# exp_5.net
KiCad netlist of a schematic drawn in EAGLE
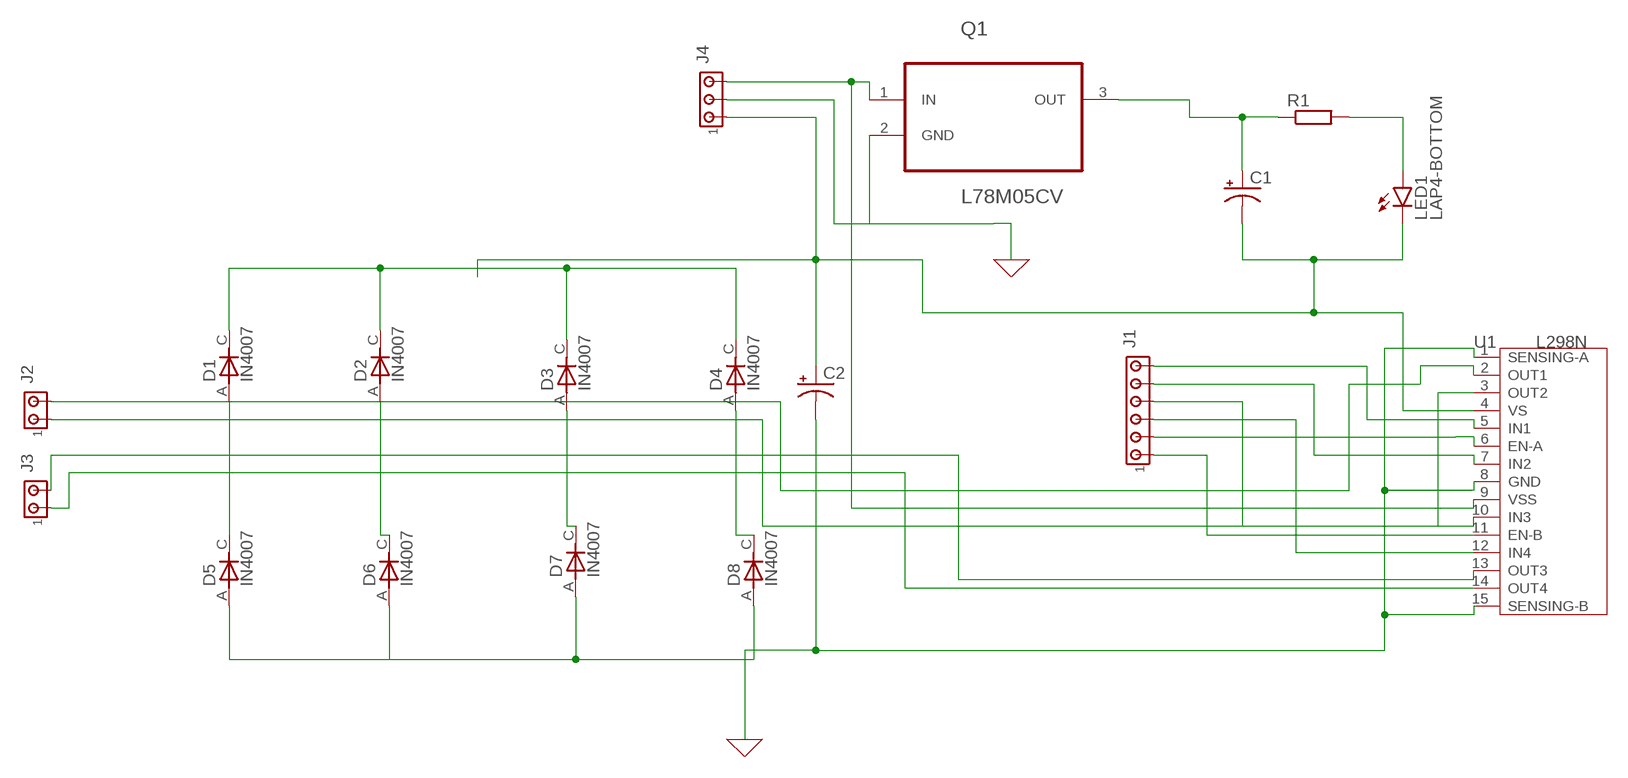
[diagram p0: schematic, sheet 1]

(export (version "E")
  (design (tool "Eeschema 10.0.6"))
  (components
    (comp (ref "C1")
      (value "CPOL-US085CS-1AR")
      (footprint "eagle-import:085CS_1AR")
      (libsource (lib "eagle-import") (part "CPOL-US085CS-1AR"))
    )
    (comp (ref "C2")
      (value "CPOL-US085CS-1AR")
      (footprint "eagle-import:085CS_1AR")
      (libsource (lib "eagle-import") (part "CPOL-US085CS-1AR"))
    )
    (comp (ref "D1")
      (value "IN4007")
      (footprint "eagle-import:DIOAD1070W78L470D235P")
      (fields (field (name "MF") "Vishay Semiconductor"))
      (libsource (lib "eagle-import") (part "IN4007"))
    )
    (comp (ref "D2")
      (value "IN4007")
      (footprint "eagle-import:DIOAD1070W78L470D235P")
      (fields (field (name "MF") "Vishay Semiconductor"))
      (libsource (lib "eagle-import") (part "IN4007"))
    )
    (comp (ref "D3")
      (value "IN4007")
      (footprint "eagle-import:DIOAD1070W78L470D235P")
      (fields (field (name "MF") "Vishay Semiconductor"))
      (libsource (lib "eagle-import") (part "IN4007"))
    )
    (comp (ref "D4")
      (value "IN4007")
      (footprint "eagle-import:DIOAD1070W78L470D235P")
      (fields (field (name "MF") "Vishay Semiconductor"))
      (libsource (lib "eagle-import") (part "IN4007"))
    )
    (comp (ref "D5")
      (value "IN4007")
      (footprint "eagle-import:DIOAD1070W78L470D235P")
      (fields (field (name "MF") "Vishay Semiconductor"))
      (libsource (lib "eagle-import") (part "IN4007"))
    )
    (comp (ref "D6")
      (value "IN4007")
      (footprint "eagle-import:DIOAD1070W78L470D235P")
      (fields (field (name "MF") "Vishay Semiconductor"))
      (libsource (lib "eagle-import") (part "IN4007"))
    )
    (comp (ref "D7")
      (value "IN4007")
      (footprint "eagle-import:DIOAD1070W78L470D235P")
      (fields (field (name "MF") "Vishay Semiconductor"))
      (libsource (lib "eagle-import") (part "IN4007"))
    )
    (comp (ref "D8")
      (value "IN4007")
      (footprint "eagle-import:DIOAD1070W78L470D235P")
      (fields (field (name "MF") "Vishay Semiconductor"))
      (libsource (lib "eagle-import") (part "IN4007"))
    )
    (comp (ref "J1")
      (value "MTA06-100")
      (footprint "eagle-import:10X06MTA")
      (libsource (lib "eagle-import") (part "MTA06-100"))
    )
    (comp (ref "J2")
      (value "MTA02-100")
      (footprint "eagle-import:10X02MTA")
      (libsource (lib "eagle-import") (part "MTA02-100"))
    )
    (comp (ref "J3")
      (value "MTA02-100")
      (footprint "eagle-import:10X02MTA")
      (libsource (lib "eagle-import") (part "MTA02-100"))
    )
    (comp (ref "J4")
      (value "MTA03-100")
      (footprint "eagle-import:10X03MTA")
      (libsource (lib "eagle-import") (part "MTA03-100"))
    )
    (comp (ref "LED1")
      (value "LAP4-BOTTOM")
      (footprint "eagle-import:P47F-BOTTOM")
      (libsource (lib "eagle-import") (part "P4-BOTTOMLA"))
    )
    (comp (ref "Q1")
      (value "L78M05CV")
      (footprint "eagle-import:TO254P450X1020X1935-3P")
      (fields (field (name "MF") "STMicroelectronics") (field (name "MP") "L78M05CV."))
      (libsource (lib "eagle-import") (part "L78M05CV"))
    )
    (comp (ref "R1")
      (value "R-EU_0204/2V")
      (footprint "eagle-import:0204V")
      (libsource (lib "eagle-import") (part "R-EU_0204/2V"))
    )
    (comp (ref "U1")
      (value "L298N")
      (footprint "eagle-import:MULTIWATT15-V")
      (fields (field (name "MF") "4tronix"))
      (libsource (lib "eagle-import") (part "L298N"))
    )
  )
  (nets
    (net (code "1") (name "GND") (class "Default")
      (node (ref "C2") (pin "-") (pinfunction "-_-") (pintype "passive"))
      (node (ref "J4") (pin "2") (pinfunction "2_2") (pintype "passive"))
      (node (ref "Q1") (pin "2") (pinfunction "GND_2") (pintype "passive"))
      (node (ref "U1") (pin "1") (pinfunction "SENSING-A_1") (pintype "bidirectional"))
      (node (ref "U1") (pin "15") (pinfunction "SENSING-B_15") (pintype "bidirectional"))
      (node (ref "U1") (pin "8") (pinfunction "GND_8") (pintype "power_in"))
    )
    (net (code "2") (name "Net-(D1-PadA)") (class "Default")
      (node (ref "D1") (pin "A") (pinfunction "A_A") (pintype "passive"))
      (node (ref "D5") (pin "C") (pinfunction "C_C") (pintype "passive"))
    )
    (net (code "3") (name "Net-(D1-PadC)") (class "Default")
      (node (ref "D1") (pin "C") (pinfunction "C_C") (pintype "passive"))
      (node (ref "D2") (pin "C") (pinfunction "C_C") (pintype "passive"))
      (node (ref "D3") (pin "C") (pinfunction "C_C") (pintype "passive"))
      (node (ref "D4") (pin "C") (pinfunction "C_C") (pintype "passive"))
    )
    (net (code "4") (name "Net-(D2-PadA)") (class "Default")
      (node (ref "D2") (pin "A") (pinfunction "A_A") (pintype "passive"))
      (node (ref "D6") (pin "C") (pinfunction "C_C") (pintype "passive"))
    )
    (net (code "5") (name "Net-(D3-PadA)") (class "Default")
      (node (ref "D3") (pin "A") (pinfunction "A_A") (pintype "passive"))
      (node (ref "D7") (pin "C") (pinfunction "C_C") (pintype "passive"))
    )
    (net (code "6") (name "Net-(D4-PadA)") (class "Default")
      (node (ref "D4") (pin "A") (pinfunction "A_A") (pintype "passive"))
      (node (ref "D8") (pin "C") (pinfunction "C_C") (pintype "passive"))
    )
    (net (code "7") (name "Net-(D5-PadA)") (class "Default")
      (node (ref "D5") (pin "A") (pinfunction "A_A") (pintype "passive"))
      (node (ref "D6") (pin "A") (pinfunction "A_A") (pintype "passive"))
      (node (ref "D7") (pin "A") (pinfunction "A_A") (pintype "passive"))
      (node (ref "D8") (pin "A") (pinfunction "A_A") (pintype "passive"))
    )
    (net (code "8") (name "Net-(LED1-PadA)") (class "Default")
      (node (ref "LED1") (pin "A") (pinfunction "A_A") (pintype "passive"))
      (node (ref "R1") (pin "2") (pinfunction "2_2") (pintype "passive"))
    )
    (net (code "9") (name "Net-(Q1-IN)") (class "Default")
      (node (ref "J4") (pin "3") (pinfunction "3_3") (pintype "passive"))
      (node (ref "Q1") (pin "1") (pinfunction "IN_1") (pintype "input"))
      (node (ref "U1") (pin "9") (pinfunction "VSS_9") (pintype "power_in"))
    )
    (net (code "10") (name "Net-(Q1-OUT)") (class "Default")
      (node (ref "C1") (pin "+") (pinfunction "+_+") (pintype "passive"))
      (node (ref "Q1") (pin "3") (pinfunction "OUT_3") (pintype "output"))
      (node (ref "R1") (pin "1") (pinfunction "1_1") (pintype "passive"))
    )
    (net (code "11") (name "Net-(U1-EN-A)") (class "Default")
      (node (ref "J1") (pin "2") (pinfunction "2_2") (pintype "passive"))
      (node (ref "U1") (pin "6") (pinfunction "EN-A_6") (pintype "input"))
    )
    (net (code "12") (name "Net-(U1-EN-B)") (class "Default")
      (node (ref "J1") (pin "1") (pinfunction "1_1") (pintype "passive"))
      (node (ref "U1") (pin "11") (pinfunction "EN-B_11") (pintype "input"))
    )
    (net (code "13") (name "Net-(U1-IN1)") (class "Default")
      (node (ref "J1") (pin "6") (pinfunction "6_6") (pintype "passive"))
      (node (ref "U1") (pin "5") (pinfunction "IN1_5") (pintype "input"))
    )
    (net (code "14") (name "Net-(U1-IN2)") (class "Default")
      (node (ref "J1") (pin "5") (pinfunction "5_5") (pintype "passive"))
      (node (ref "U1") (pin "7") (pinfunction "IN2_7") (pintype "input"))
    )
    (net (code "15") (name "Net-(U1-IN3)") (class "Default")
      (node (ref "J1") (pin "4") (pinfunction "4_4") (pintype "passive"))
      (node (ref "U1") (pin "10") (pinfunction "IN3_10") (pintype "input"))
    )
    (net (code "16") (name "Net-(U1-IN4)") (class "Default")
      (node (ref "J1") (pin "3") (pinfunction "3_3") (pintype "passive"))
      (node (ref "U1") (pin "12") (pinfunction "IN4_12") (pintype "input"))
    )
    (net (code "17") (name "Net-(U1-OUT1)") (class "Default")
      (node (ref "J2") (pin "2") (pinfunction "2_2") (pintype "passive"))
      (node (ref "U1") (pin "2") (pinfunction "OUT1_2") (pintype "output"))
    )
    (net (code "18") (name "Net-(U1-OUT2)") (class "Default")
      (node (ref "J2") (pin "1") (pinfunction "1_1") (pintype "passive"))
      (node (ref "U1") (pin "3") (pinfunction "OUT2_3") (pintype "output"))
    )
    (net (code "19") (name "Net-(U1-OUT3)") (class "Default")
      (node (ref "J3") (pin "2") (pinfunction "2_2") (pintype "passive"))
      (node (ref "U1") (pin "13") (pinfunction "OUT3_13") (pintype "output"))
    )
    (net (code "20") (name "Net-(U1-OUT4)") (class "Default")
      (node (ref "J3") (pin "1") (pinfunction "1_1") (pintype "passive"))
      (node (ref "U1") (pin "14") (pinfunction "OUT4_14") (pintype "output"))
    )
    (net (code "21") (name "Net-(U1-VS)") (class "Default")
      (node (ref "C1") (pin "-") (pinfunction "-_-") (pintype "passive"))
      (node (ref "C2") (pin "+") (pinfunction "+_+") (pintype "passive"))
      (node (ref "J4") (pin "1") (pinfunction "1_1") (pintype "passive"))
      (node (ref "LED1") (pin "C") (pinfunction "C_C") (pintype "passive"))
      (node (ref "U1") (pin "4") (pinfunction "VS_4") (pintype "power_in"))
    )
  )
)
